# USB_OTG_FS.net
KiCad netlist of a schematic drawn in Altium Designer
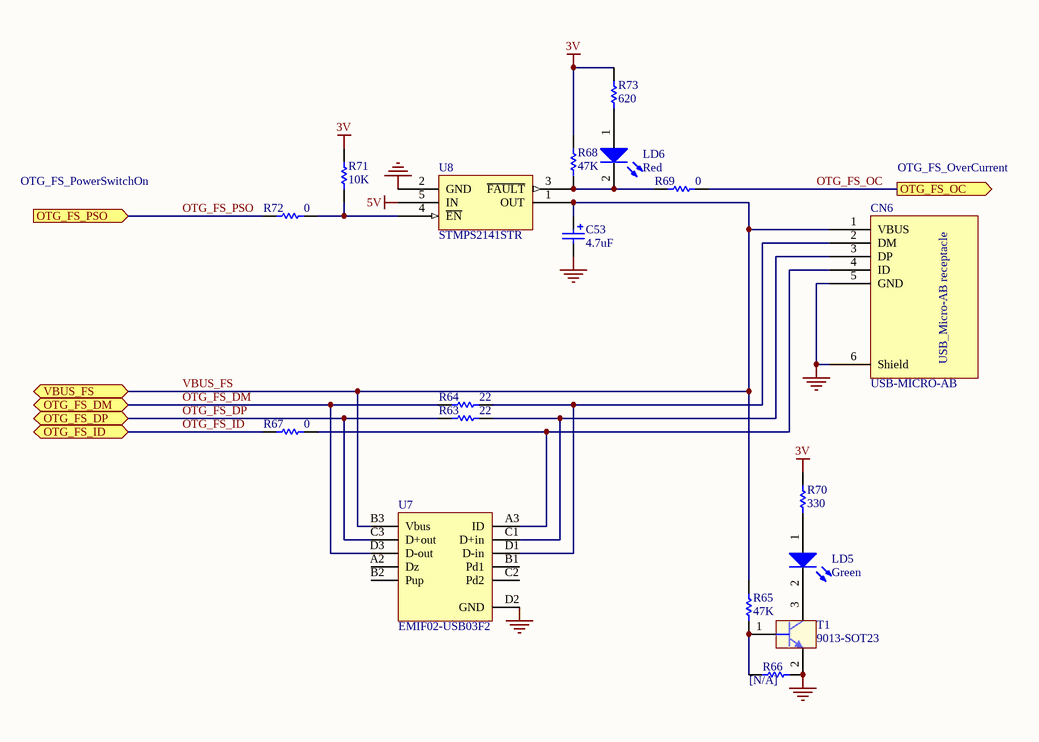
[diagram p0: USB_OTG_FS.SchDoc]

(export (version "E")
  (design (tool "Eeschema 10.0.6"))
  (components
    (comp (ref "C53")
      (value "4.7uF")
      (footprint "TAN-A")
      (description "Polarized Capacitor (Radial)")
      (fields (field (name "PUBLISHER") "Altium Limited"))
      (libsource (lib "Miscellaneous Devices") (part "Cap Pol1"))
    )
    (comp (ref "CN6")
      (value "USB-MICRO-AB")
      (footprint "USB-MICRO-AB")
      (description "USB-MICRO-AB, 47590-0001, SMT, MOLEX")
      (libsource (lib "MCD_TOOLS") (part "USB-MICRO-AB"))
    )
    (comp (ref "LD5")
      (value "Green")
      (footprint "0603D")
      (description "Typical RED, GREEN, YELLOW, AMBER GaAs LED")
      (fields (field (name "PUBLISHER") "Altium Limited"))
      (libsource (lib "Miscellaneous Devices") (part "LED2"))
    )
    (comp (ref "LD6")
      (value "Red")
      (footprint "0603D")
      (description "Typical RED, GREEN, YELLOW, AMBER GaAs LED")
      (fields (field (name "PUBLISHER") "Altium Limited"))
      (libsource (lib "Miscellaneous Devices") (part "LED2"))
    )
    (comp (ref "R63")
      (value "22")
      (footprint "0402R")
      (description "Resistor 0402 / 0603 / 0805")
      (libsource (lib "MCD_TOOLS") (part "Resistor_ST"))
    )
    (comp (ref "R64")
      (value "22")
      (footprint "0402R")
      (description "Resistor 0402 / 0603 / 0805")
      (libsource (lib "MCD_TOOLS") (part "Resistor_ST"))
    )
    (comp (ref "R65")
      (value "47K")
      (footprint "0402R")
      (description "Resistor 0402 / 0603 / 0805")
      (libsource (lib "MCD_TOOLS") (part "Resistor_ST"))
    )
    (comp (ref "R66")
      (value "[N/A]")
      (footprint "0402R")
      (description "Resistor 0402 / 0603 / 0805")
      (libsource (lib "MCD_TOOLS") (part "Resistor_ST"))
    )
    (comp (ref "R67")
      (value "0")
      (footprint "0402R")
      (description "Resistor 0402 / 0603 / 0805")
      (libsource (lib "MCD_TOOLS") (part "Resistor_ST"))
    )
    (comp (ref "R68")
      (value "47K")
      (footprint "0402R")
      (description "Resistor 0402 / 0603 / 0805")
      (libsource (lib "MCD_TOOLS") (part "Resistor_ST"))
    )
    (comp (ref "R69")
      (value "0")
      (footprint "0402R")
      (description "Resistor 0402 / 0603 / 0805")
      (libsource (lib "MCD_TOOLS") (part "Resistor_ST"))
    )
    (comp (ref "R70")
      (value "330")
      (footprint "0603R")
      (description "Resistor 0402 / 0603 / 0805")
      (libsource (lib "MCD_TOOLS") (part "Resistor_ST"))
    )
    (comp (ref "R71")
      (value "10K")
      (footprint "0402R")
      (description "Resistor 0402 / 0603 / 0805")
      (libsource (lib "MCD_TOOLS") (part "Resistor_ST"))
    )
    (comp (ref "R72")
      (value "0")
      (footprint "0402R")
      (description "Resistor 0402 / 0603 / 0805")
      (libsource (lib "MCD_TOOLS") (part "Resistor_ST"))
    )
    (comp (ref "R73")
      (value "620")
      (footprint "0603R")
      (description "Resistor 0402 / 0603 / 0805")
      (libsource (lib "MCD_TOOLS") (part "Resistor_ST"))
    )
    (comp (ref "T1")
      (value "9013-SOT23")
      (footprint "SOT-23")
      (description "NPN Bipolar Transistor")
      (libsource (lib "MCD_TOOLS") (part "9013-SOT23"))
    )
    (comp (ref "U7")
      (value "EMIF02-USB03F2")
      (footprint "Flip Chip")
      (description "2-line IPAD, EMI filter including ESD protection")
      (libsource (lib "MCD_TOOLS") (part "EMIF02-USB03F2"))
    )
    (comp (ref "U8")
      (value "STMPS2141STR")
      (footprint "SOT23-5L")
      (description "Enhanced single channel power switches")
      (libsource (lib "MCD_TOOLS") (part "STMPS2141STR"))
    )
  )
  (nets
    (net (code "1") (name "/OTG_FS_DM") (class "Default")
      (node (ref "R64") (pin "1") (pinfunction "1_1") (pintype "passive"))
      (node (ref "U7") (pin "D3") (pinfunction "D-out_D3") (pintype "passive"))
    )
    (net (code "2") (name "/OTG_FS_DP") (class "Default")
      (node (ref "R63") (pin "1") (pinfunction "1_1") (pintype "passive"))
      (node (ref "U7") (pin "C3") (pinfunction "D+out_C3") (pintype "passive"))
    )
    (net (code "3") (name "/OTG_FS_ID") (class "Default")
      (node (ref "R67") (pin "1") (pinfunction "1_1") (pintype "passive"))
    )
    (net (code "4") (name "/OTG_FS_OC") (class "Default")
      (node (ref "R69") (pin "2") (pinfunction "2_2") (pintype "passive"))
    )
    (net (code "5") (name "/OTG_FS_PSO") (class "Default")
      (node (ref "R72") (pin "1") (pinfunction "1_1") (pintype "passive"))
    )
    (net (code "6") (name "/VBUS_FS") (class "Default")
      (node (ref "C53") (pin "1") (pinfunction "1_1") (pintype "passive"))
      (node (ref "CN6") (pin "1") (pinfunction "VBUS_1") (pintype "passive"))
      (node (ref "R65") (pin "2") (pinfunction "2_2") (pintype "passive"))
      (node (ref "U7") (pin "B3") (pinfunction "Vbus_B3") (pintype "passive"))
      (node (ref "U8") (pin "1") (pinfunction "OUT_1") (pintype "passive"))
    )
    (net (code "7") (name "3V") (class "Default")
      (node (ref "R68") (pin "2") (pinfunction "2_2") (pintype "passive"))
      (node (ref "R70") (pin "2") (pinfunction "2_2") (pintype "passive"))
      (node (ref "R71") (pin "2") (pinfunction "2_2") (pintype "passive"))
      (node (ref "R73") (pin "2") (pinfunction "2_2") (pintype "passive"))
    )
    (net (code "8") (name "5V") (class "Default")
      (node (ref "U8") (pin "5") (pinfunction "IN_5") (pintype "passive"))
    )
    (net (code "9") (name "GND") (class "Default")
      (node (ref "C53") (pin "2") (pinfunction "2_2") (pintype "passive"))
      (node (ref "CN6") (pin "5") (pinfunction "GND_5") (pintype "passive"))
      (node (ref "CN6") (pin "6") (pinfunction "Shield_6") (pintype "passive"))
      (node (ref "R66") (pin "2") (pinfunction "2_2") (pintype "passive"))
      (node (ref "T1") (pin "2") (pinfunction "E_2") (pintype "passive"))
      (node (ref "U7") (pin "D2") (pinfunction "GND_D2") (pintype "passive"))
      (node (ref "U8") (pin "2") (pinfunction "GND_2") (pintype "passive"))
    )
    (net (code "10") (name "Net-(CN6-DM)") (class "Default")
      (node (ref "CN6") (pin "2") (pinfunction "DM_2") (pintype "passive"))
      (node (ref "R64") (pin "2") (pinfunction "2_2") (pintype "passive"))
      (node (ref "U7") (pin "D1") (pinfunction "D-in_D1") (pintype "passive"))
    )
    (net (code "11") (name "Net-(CN6-DP)") (class "Default")
      (node (ref "CN6") (pin "3") (pinfunction "DP_3") (pintype "passive"))
      (node (ref "R63") (pin "2") (pinfunction "2_2") (pintype "passive"))
      (node (ref "U7") (pin "C1") (pinfunction "D+in_C1") (pintype "passive"))
    )
    (net (code "12") (name "Net-(CN6-ID)") (class "Default")
      (node (ref "CN6") (pin "4") (pinfunction "ID_4") (pintype "passive"))
      (node (ref "R67") (pin "2") (pinfunction "2_2") (pintype "passive"))
      (node (ref "U7") (pin "A3") (pinfunction "ID_A3") (pintype "passive"))
    )
    (net (code "13") (name "Net-(LD5-A)") (class "Default")
      (node (ref "LD5") (pin "1") (pinfunction "A_1") (pintype "passive"))
      (node (ref "R70") (pin "1") (pinfunction "1_1") (pintype "passive"))
    )
    (net (code "14") (name "Net-(LD5-K)") (class "Default")
      (node (ref "LD5") (pin "2") (pinfunction "K_2") (pintype "passive"))
      (node (ref "T1") (pin "3") (pinfunction "C_3") (pintype "passive"))
    )
    (net (code "15") (name "Net-(LD6-A)") (class "Default")
      (node (ref "LD6") (pin "1") (pinfunction "A_1") (pintype "passive"))
      (node (ref "R73") (pin "1") (pinfunction "1_1") (pintype "passive"))
    )
    (net (code "16") (name "Net-(LD6-K)") (class "Default")
      (node (ref "LD6") (pin "2") (pinfunction "K_2") (pintype "passive"))
      (node (ref "R68") (pin "1") (pinfunction "1_1") (pintype "passive"))
      (node (ref "R69") (pin "1") (pinfunction "1_1") (pintype "passive"))
      (node (ref "U8") (pin "3") (pinfunction "~{FAULT}_3") (pintype "output"))
    )
    (net (code "17") (name "Net-(T1-B)") (class "Default")
      (node (ref "R65") (pin "1") (pinfunction "1_1") (pintype "passive"))
      (node (ref "R66") (pin "1") (pinfunction "1_1") (pintype "passive"))
      (node (ref "T1") (pin "1") (pinfunction "B_1") (pintype "passive"))
    )
    (net (code "18") (name "Net-(U8-~{EN})") (class "Default")
      (node (ref "R71") (pin "1") (pinfunction "1_1") (pintype "passive"))
      (node (ref "R72") (pin "2") (pinfunction "2_2") (pintype "passive"))
      (node (ref "U8") (pin "4") (pinfunction "~{EN}_4") (pintype "input"))
    )
    (net (code "19") (name "unconnected-(U7-Dz-PadA2)") (class "Default")
      (node (ref "U7") (pin "A2") (pinfunction "Dz_A2") (pintype "passive"))
    )
    (net (code "20") (name "unconnected-(U7-Pd1-PadB1)") (class "Default")
      (node (ref "U7") (pin "B1") (pinfunction "Pd1_B1") (pintype "passive"))
    )
    (net (code "21") (name "unconnected-(U7-Pd2-PadC2)") (class "Default")
      (node (ref "U7") (pin "C2") (pinfunction "Pd2_C2") (pintype "passive"))
    )
    (net (code "22") (name "unconnected-(U7-Pup-PadB2)") (class "Default")
      (node (ref "U7") (pin "B2") (pinfunction "Pup_B2") (pintype "passive"))
    )
  )
)
